# MainBoard_MCU_Power.net
KiCad netlist of a schematic drawn in Altium Designer
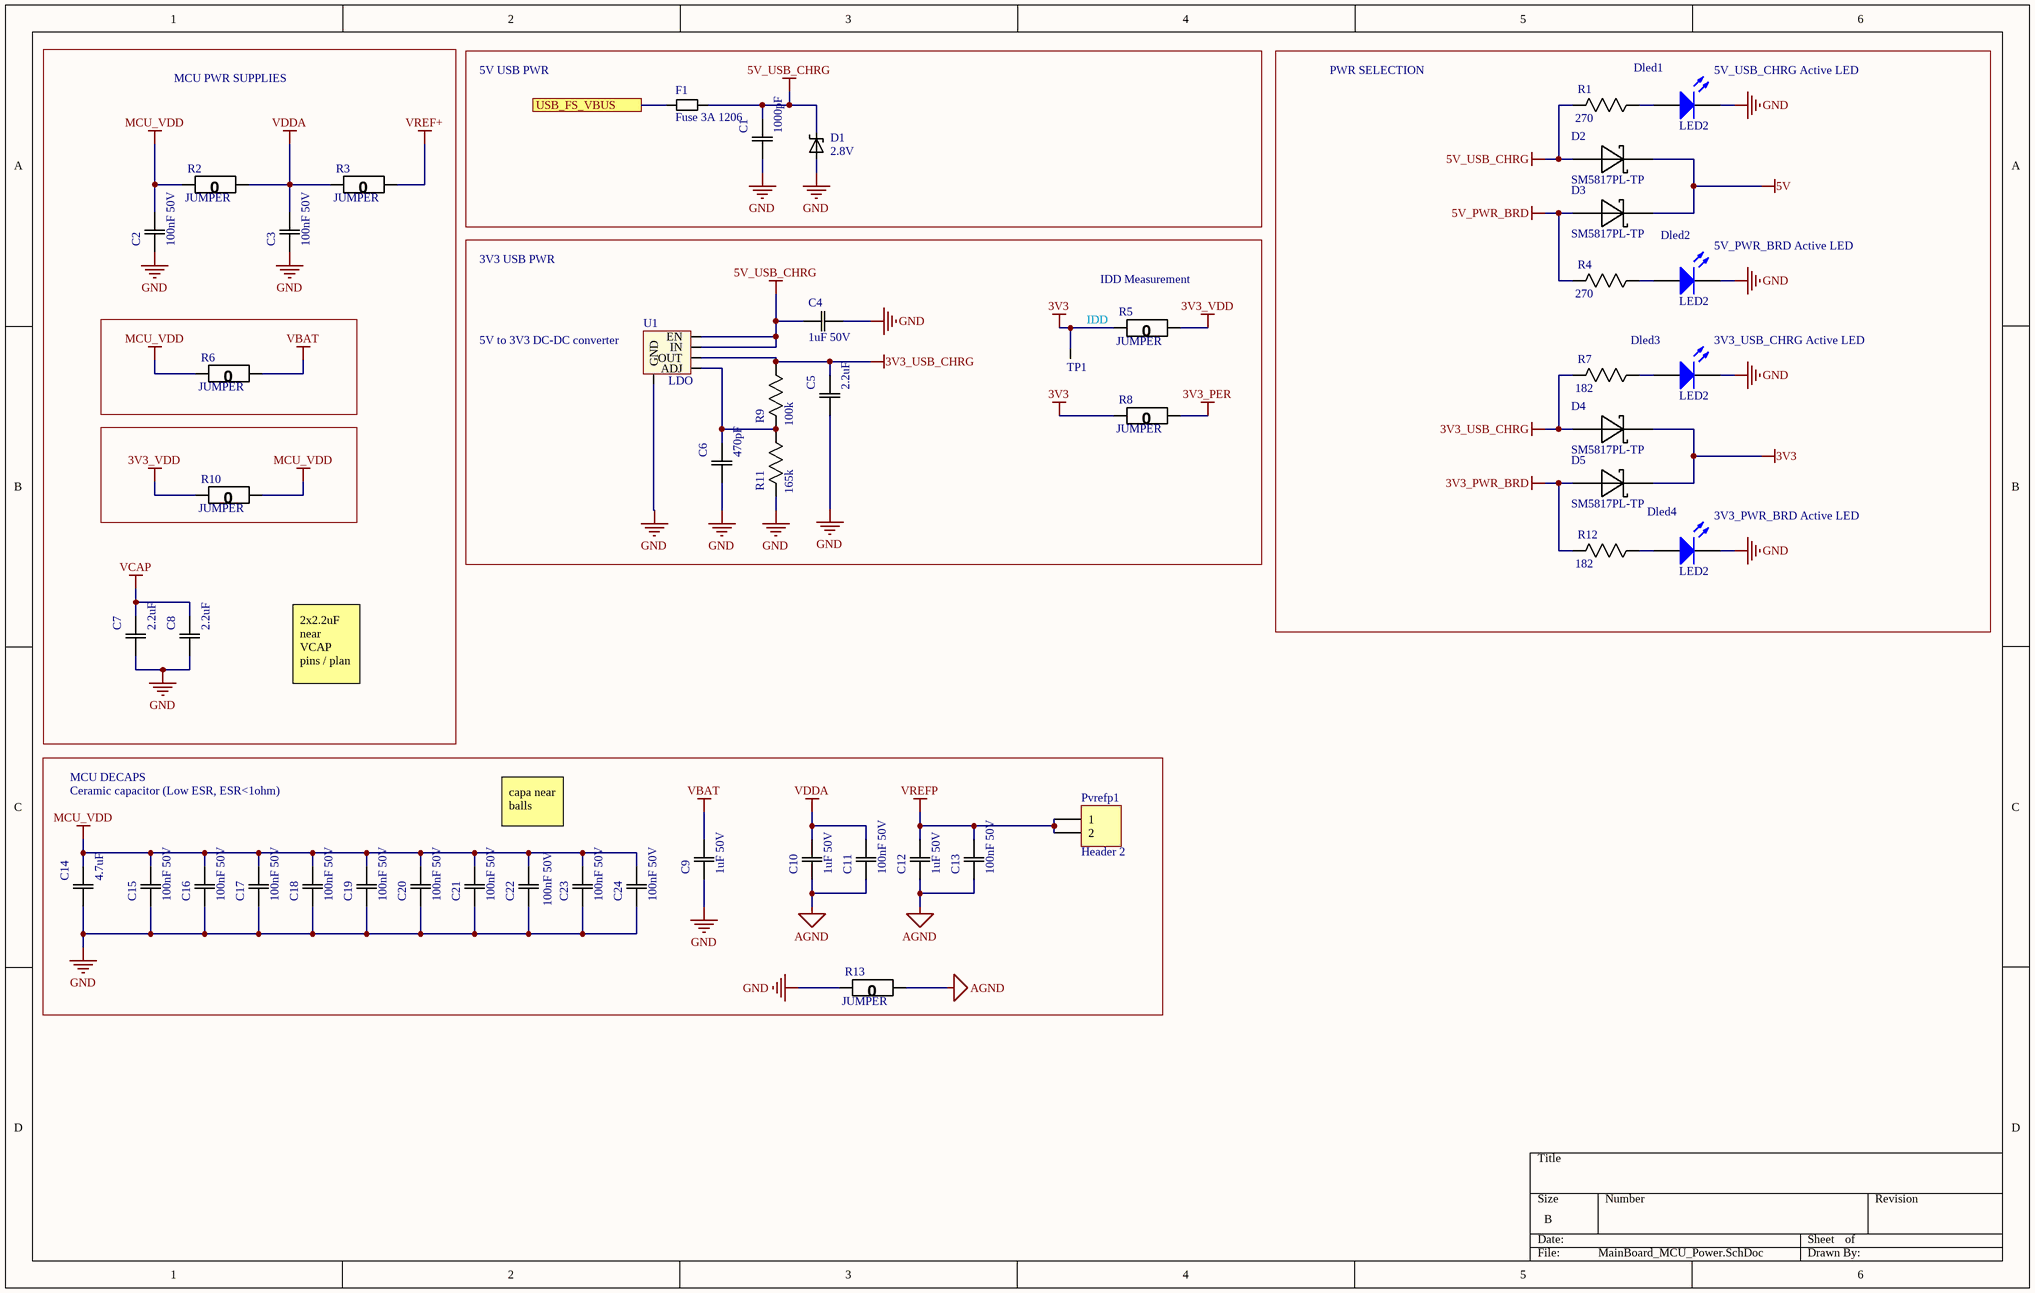
[diagram p0: MainBoard_MCU_Power.SchDoc]

(export (version "E")
  (design (tool "Eeschema 10.0.6"))
  (components
    (comp (ref "C1")
      (value "1000pF")
      (footprint "0805")
      (description "CAP CER 1000PF 50V X7R 0603/0805")
      (fields (field (name "TOLERANCE") "10%"))
      (libsource (lib "AltiumLibraries") (part "CAP 1000pF 50V"))
    )
    (comp (ref "C2")
      (value "100nF 50V")
      (footprint "0805")
      (description "CAP CER 0.1UF 50V X7R 0805")
      (fields (field (name "TOLERANCE") "10%"))
      (libsource (lib "AltiumLibraries") (part "CAP 100nF 50V"))
    )
    (comp (ref "C3")
      (value "100nF 50V")
      (footprint "0805")
      (description "CAP CER 0.1UF 50V X7R 0805")
      (fields (field (name "TOLERANCE") "10%"))
      (libsource (lib "AltiumLibraries") (part "CAP 100nF 50V"))
    )
    (comp (ref "C4")
      (value "1uF 50V")
      (footprint "0805")
      (description "CAP CER 1UF 50V X7R 0805")
      (fields (field (name "TOLERANCE") "10%"))
      (libsource (lib "AltiumLibraries") (part "CAP 1uF 50V"))
    )
    (comp (ref "C5")
      (value "2.2uF")
      (footprint "0805")
      (description "CAP CER 2.2UF 35V X7R 0603/0805")
      (fields (field (name "TOLERANCE") "10%"))
      (libsource (lib "") (part "CAP 2.2uF 35V_1"))
    )
    (comp (ref "C6")
      (value "470pF")
      (footprint "0805")
      (description "CAP CER 470PF 50V X7R 0603/0805")
      (fields (field (name "TOLERANCE") "10%"))
      (libsource (lib "AltiumLibraries") (part "CAP 470pF 50V"))
    )
    (comp (ref "C7")
      (value "2.2uF")
      (footprint "0805")
      (description "CAP CER 2.2UF 35V X7R 0603/0805")
      (fields (field (name "TOLERANCE") "10%"))
      (libsource (lib "AltiumLibraries") (part "CAP 2.2uF 35V"))
    )
    (comp (ref "C8")
      (value "2.2uF")
      (footprint "0805")
      (description "CAP CER 2.2UF 35V X7R 0603/0805")
      (fields (field (name "TOLERANCE") "10%"))
      (libsource (lib "AltiumLibraries") (part "CAP 2.2uF 35V"))
    )
    (comp (ref "C9")
      (value "1uF 50V")
      (footprint "0805")
      (description "CAP CER 1UF 50V X7R 0805")
      (fields (field (name "TOLERANCE") "10%"))
      (libsource (lib "AltiumLibraries") (part "CAP 1uF 50V"))
    )
    (comp (ref "C10")
      (value "1uF 50V")
      (footprint "0805")
      (description "CAP CER 1UF 50V X7R 0805")
      (fields (field (name "TOLERANCE") "10%"))
      (libsource (lib "AltiumLibraries") (part "CAP 1uF 50V"))
    )
    (comp (ref "C11")
      (value "100nF 50V")
      (footprint "0805")
      (description "CAP CER 0.1UF 50V X7R 0805")
      (fields (field (name "TOLERANCE") "10%"))
      (libsource (lib "AltiumLibraries") (part "CAP 100nF 50V"))
    )
    (comp (ref "C12")
      (value "1uF 50V")
      (footprint "0805")
      (description "CAP CER 1UF 50V X7R 0805")
      (fields (field (name "TOLERANCE") "10%"))
      (libsource (lib "AltiumLibraries") (part "CAP 1uF 50V"))
    )
    (comp (ref "C13")
      (value "100nF 50V")
      (footprint "0805")
      (description "CAP CER 0.1UF 50V X7R 0805")
      (fields (field (name "TOLERANCE") "10%"))
      (libsource (lib "AltiumLibraries") (part "CAP 100nF 50V"))
    )
    (comp (ref "C14")
      (value "4.7uF")
      (footprint "0805")
      (description "CAP CER 4.7UF 35V X7R 0603/0805")
      (fields (field (name "TOLERANCE") "10%"))
      (libsource (lib "AltiumLibraries") (part "CAP 4.7uF 35V"))
    )
    (comp (ref "C15")
      (value "100nF 50V")
      (footprint "0805")
      (description "CAP CER 0.1UF 50V X7R 0805")
      (fields (field (name "TOLERANCE") "10%"))
      (libsource (lib "AltiumLibraries") (part "CAP 100nF 50V"))
    )
    (comp (ref "C16")
      (value "100nF 50V")
      (footprint "0805")
      (description "CAP CER 0.1UF 50V X7R 0805")
      (fields (field (name "TOLERANCE") "10%"))
      (libsource (lib "AltiumLibraries") (part "CAP 100nF 50V"))
    )
    (comp (ref "C17")
      (value "100nF 50V")
      (footprint "0805")
      (description "CAP CER 0.1UF 50V X7R 0805")
      (fields (field (name "TOLERANCE") "10%"))
      (libsource (lib "AltiumLibraries") (part "CAP 100nF 50V"))
    )
    (comp (ref "C18")
      (value "100nF 50V")
      (footprint "0805")
      (description "CAP CER 0.1UF 50V X7R 0805")
      (fields (field (name "TOLERANCE") "10%"))
      (libsource (lib "AltiumLibraries") (part "CAP 100nF 50V"))
    )
    (comp (ref "C19")
      (value "100nF 50V")
      (footprint "0805")
      (description "CAP CER 0.1UF 50V X7R 0805")
      (fields (field (name "TOLERANCE") "10%"))
      (libsource (lib "AltiumLibraries") (part "CAP 100nF 50V"))
    )
    (comp (ref "C20")
      (value "100nF 50V")
      (footprint "0805")
      (description "CAP CER 0.1UF 50V X7R 0805")
      (fields (field (name "TOLERANCE") "10%"))
      (libsource (lib "AltiumLibraries") (part "CAP 100nF 50V"))
    )
    (comp (ref "C21")
      (value "100nF 50V")
      (footprint "0805")
      (description "CAP CER 0.1UF 50V X7R 0805")
      (fields (field (name "TOLERANCE") "10%"))
      (libsource (lib "AltiumLibraries") (part "CAP 100nF 50V"))
    )
    (comp (ref "C22")
      (value "100nF 50V")
      (footprint "0805")
      (description "CAP CER 0.1UF 50V X7R 0805")
      (fields (field (name "TOLERANCE") "10%"))
      (libsource (lib "AltiumLibraries") (part "CAP 100nF 50V"))
    )
    (comp (ref "C23")
      (value "100nF 50V")
      (footprint "0805")
      (description "CAP CER 0.1UF 50V X7R 0805")
      (fields (field (name "TOLERANCE") "10%"))
      (libsource (lib "AltiumLibraries") (part "CAP 100nF 50V"))
    )
    (comp (ref "C24")
      (value "100nF 50V")
      (footprint "0805")
      (description "CAP CER 0.1UF 50V X7R 0805")
      (fields (field (name "TOLERANCE") "10%"))
      (libsource (lib "AltiumLibraries") (part "CAP 100nF 50V"))
    )
    (comp (ref "D1")
      (value "2.8V")
      (footprint "SOD-123")
      (description "Zener Diode 2.8V 500mW ±5% Surface Mount SOD-123")
      (libsource (lib "AltiumLibraries") (part "DIODE ZENER 2.8V 500mW"))
    )
    (comp (ref "D2")
      (value "SM5817PL-TP")
      (footprint "SOD-123")
      (description "Diode Schottky 20V 1A Surface Mount SOD-123FL")
      (fields (field (name "MF") "Micro Commercial Co"))
      (libsource (lib "AltiumLibraries") (part "DIODE SCHOTTKY 20V 1A"))
    )
    (comp (ref "D3")
      (value "SM5817PL-TP")
      (footprint "SOD-123")
      (description "Diode Schottky 20V 1A Surface Mount SOD-123FL")
      (fields (field (name "MF") "Micro Commercial Co"))
      (libsource (lib "AltiumLibraries") (part "DIODE SCHOTTKY 20V 1A"))
    )
    (comp (ref "D4")
      (value "SM5817PL-TP")
      (footprint "SOD-123")
      (description "Diode Schottky 20V 1A Surface Mount SOD-123FL")
      (fields (field (name "MF") "Micro Commercial Co"))
      (libsource (lib "AltiumLibraries") (part "DIODE SCHOTTKY 20V 1A"))
    )
    (comp (ref "D5")
      (value "SM5817PL-TP")
      (footprint "SOD-123")
      (description "Diode Schottky 20V 1A Surface Mount SOD-123FL")
      (fields (field (name "MF") "Micro Commercial Co"))
      (libsource (lib "AltiumLibraries") (part "DIODE SCHOTTKY 20V 1A"))
    )
    (comp (ref "Dled1")
      (value "LED2")
      (footprint "3.2X1.6X1.1")
      (description "Typical RED, GREEN, YELLOW, AMBER GaAs LED")
      (libsource (lib "AltiumLibraries") (part "LED GREEN SMD"))
    )
    (comp (ref "Dled2")
      (value "LED2")
      (footprint "3.2X1.6X1.1")
      (description "Typical RED, GREEN, YELLOW, AMBER GaAs LED")
      (libsource (lib "AltiumLibraries") (part "LED GREEN SMD"))
    )
    (comp (ref "Dled3")
      (value "LED2")
      (footprint "3.2X1.6X1.1")
      (description "Typical RED, GREEN, YELLOW, AMBER GaAs LED")
      (libsource (lib "AltiumLibraries") (part "LED GREEN SMD"))
    )
    (comp (ref "Dled4")
      (value "LED2")
      (footprint "3.2X1.6X1.1")
      (description "Typical RED, GREEN, YELLOW, AMBER GaAs LED")
      (libsource (lib "AltiumLibraries") (part "LED GREEN SMD"))
    )
    (comp (ref "F1")
      (value "Fuse 3A 1206")
      (footprint "1206")
      (description "FUSE 3A 63V AC/DC SLOW 1206")
      (libsource (lib "AltiumLibraries") (part "FUSE 3A 63V SLOW"))
    )
    (comp (ref "Pvrefp1")
      (value "Header 2")
      (footprint "HDR1X2")
      (description "Header, 2-Pin")
      (fields (field (name "PUBLISHER") "Altium Limited"))
      (libsource (lib "Miscellaneous Connectors") (part "Header 2"))
    )
    (comp (ref "R1")
      (value "270")
      (footprint "0805")
      (description "RES SMD 270 OHM 5% 1/8W 0805")
      (fields (field (name "TOLERANCE") "5%"))
      (libsource (lib "AltiumLibraries") (part "RES 270.0 1/8W"))
    )
    (comp (ref "R2")
      (value "JUMPER")
      (footprint "0805")
      (description "RES SMD 0 OHM JUMPER GENERIC 0805")
      (libsource (lib "AltiumLibraries") (part "RES 0 JUMPER"))
    )
    (comp (ref "R3")
      (value "JUMPER")
      (footprint "0805")
      (description "RES SMD 0 OHM JUMPER GENERIC 0805")
      (libsource (lib "AltiumLibraries") (part "RES 0 JUMPER"))
    )
    (comp (ref "R4")
      (value "270")
      (footprint "0805")
      (description "RES SMD 270 OHM 5% 1/8W 0805")
      (fields (field (name "TOLERANCE") "5%"))
      (libsource (lib "AltiumLibraries") (part "RES 270.0 1/8W"))
    )
    (comp (ref "R5")
      (value "JUMPER")
      (footprint "0805")
      (description "RES SMD 0 OHM JUMPER GENERIC 0805")
      (libsource (lib "AltiumLibraries") (part "RES 0 JUMPER"))
    )
    (comp (ref "R6")
      (value "JUMPER")
      (footprint "0805")
      (description "RES SMD 0 OHM JUMPER GENERIC 0805")
      (libsource (lib "AltiumLibraries") (part "RES 0 JUMPER"))
    )
    (comp (ref "R7")
      (value "182")
      (footprint "0805")
      (description "RES SMD 182 OHM 1% 1/8W 0805")
      (fields (field (name "TOLERANCE") "1%"))
      (libsource (lib "AltiumLibraries") (part "RES 182.0 1/8W"))
    )
    (comp (ref "R8")
      (value "JUMPER")
      (footprint "0805")
      (description "RES SMD 0 OHM JUMPER GENERIC 0805")
      (libsource (lib "AltiumLibraries") (part "RES 0 JUMPER"))
    )
    (comp (ref "R9")
      (value "100k")
      (footprint "0805")
      (description "RES SMD 100K OHM 5% 1/8W 0805")
      (fields (field (name "TOLERANCE") "5%"))
      (libsource (lib "AltiumLibraries") (part "RES 100k 1/8W - 5%"))
    )
    (comp (ref "R10")
      (value "JUMPER")
      (footprint "0805")
      (description "RES SMD 0 OHM JUMPER GENERIC 0805")
      (libsource (lib "AltiumLibraries") (part "RES 0 JUMPER"))
    )
    (comp (ref "R11")
      (value "165k")
      (footprint "0805")
      (description "RES SMD 165K OHM 1% 1/4W 0805")
      (fields (field (name "TOLERANCE") "1%"))
      (libsource (lib "AltiumLibraries") (part "RES 165k 1/4W"))
    )
    (comp (ref "R12")
      (value "182")
      (footprint "0805")
      (description "RES SMD 182 OHM 1% 1/8W 0805")
      (fields (field (name "TOLERANCE") "1%"))
      (libsource (lib "AltiumLibraries") (part "RES 182.0 1/8W"))
    )
    (comp (ref "R13")
      (value "JUMPER")
      (footprint "0805")
      (description "RES SMD 0 OHM JUMPER GENERIC 0805")
      (libsource (lib "AltiumLibraries") (part "RES 0 JUMPER"))
    )
    (comp (ref "TP1")
      (value "Test Point (Via)")
      (footprint "TP")
      (libsource (lib "AltiumLibraries") (part "Test Point (Via)"))
    )
    (comp (ref "U1")
      (value "LDO")
      (footprint "REG LIN POS ADJ 500MA 8SOIC")
      (description "Linear Voltage Regulator IC  1 Output  500mA 8-SOIC")
      (fields (field (name "MF") "Texas Instruments") (field (name "MP") "TL5209DR"))
      (libsource (lib "AltiumLibraries") (part "REG LIN POS ADJ"))
    )
  )
  (nets
    (net (code "1") (name "/USB_FS_VBUS") (class "Default")
      (node (ref "F1") (pin "1") (pinfunction "1_1") (pintype "passive"))
    )
    (net (code "2") (name "3V3") (class "Default")
      (node (ref "D4") (pin "C") (pinfunction "K_C") (pintype "passive"))
      (node (ref "D5") (pin "C") (pinfunction "K_C") (pintype "passive"))
      (node (ref "R5") (pin "2") (pinfunction "R2_2") (pintype "passive"))
      (node (ref "R8") (pin "2") (pinfunction "R2_2") (pintype "passive"))
      (node (ref "TP1") (pin "1") (pinfunction "1_1") (pintype "passive"))
    )
    (net (code "3") (name "3V3_PER") (class "Default")
      (node (ref "R8") (pin "1") (pinfunction "R1_1") (pintype "passive"))
    )
    (net (code "4") (name "3V3_PWR_BRD") (class "Default")
      (node (ref "D5") (pin "A") (pinfunction "A_A") (pintype "passive"))
      (node (ref "R12") (pin "2") (pinfunction "R2_2") (pintype "passive"))
    )
    (net (code "5") (name "3V3_USB_CHRG") (class "Default")
      (node (ref "C5") (pin "2") (pinfunction "C2_2") (pintype "passive"))
      (node (ref "D4") (pin "A") (pinfunction "A_A") (pintype "passive"))
      (node (ref "R7") (pin "2") (pinfunction "R2_2") (pintype "passive"))
      (node (ref "R9") (pin "1") (pinfunction "R1_1") (pintype "passive"))
      (node (ref "U1") (pin "OUT") (pinfunction "OUT_OUT") (pintype "passive"))
    )
    (net (code "6") (name "3V3_VDD") (class "Default")
      (node (ref "R10") (pin "2") (pinfunction "R2_2") (pintype "passive"))
      (node (ref "R5") (pin "1") (pinfunction "R1_1") (pintype "passive"))
    )
    (net (code "7") (name "5V") (class "Default")
      (node (ref "D2") (pin "C") (pinfunction "K_C") (pintype "passive"))
      (node (ref "D3") (pin "C") (pinfunction "K_C") (pintype "passive"))
    )
    (net (code "8") (name "5V_PWR_BRD") (class "Default")
      (node (ref "D3") (pin "A") (pinfunction "A_A") (pintype "passive"))
      (node (ref "R4") (pin "2") (pinfunction "R2_2") (pintype "passive"))
    )
    (net (code "9") (name "5V_USB_CHRG") (class "Default")
      (node (ref "C1") (pin "2") (pinfunction "C2_2") (pintype "passive"))
      (node (ref "C4") (pin "1") (pinfunction "C1_1") (pintype "passive"))
      (node (ref "D1") (pin "C") (pinfunction "C_C") (pintype "passive"))
      (node (ref "D2") (pin "A") (pinfunction "A_A") (pintype "passive"))
      (node (ref "F1") (pin "2") (pinfunction "2_2") (pintype "passive"))
      (node (ref "R1") (pin "2") (pinfunction "R2_2") (pintype "passive"))
      (node (ref "U1") (pin "EN") (pinfunction "EN_EN") (pintype "passive"))
      (node (ref "U1") (pin "IN") (pinfunction "IN_IN") (pintype "passive"))
    )
    (net (code "10") (name "AGND") (class "Default")
      (node (ref "C10") (pin "1") (pinfunction "C1_1") (pintype "passive"))
      (node (ref "C11") (pin "1") (pinfunction "C1_1") (pintype "passive"))
      (node (ref "C12") (pin "1") (pinfunction "C1_1") (pintype "passive"))
      (node (ref "C13") (pin "1") (pinfunction "C1_1") (pintype "passive"))
      (node (ref "R13") (pin "1") (pinfunction "R1_1") (pintype "passive"))
    )
    (net (code "11") (name "GND") (class "Default")
      (node (ref "C1") (pin "1") (pinfunction "C1_1") (pintype "passive"))
      (node (ref "C14") (pin "1") (pinfunction "C1_1") (pintype "passive"))
      (node (ref "C15") (pin "1") (pinfunction "C1_1") (pintype "passive"))
      (node (ref "C16") (pin "1") (pinfunction "C1_1") (pintype "passive"))
      (node (ref "C17") (pin "1") (pinfunction "C1_1") (pintype "passive"))
      (node (ref "C18") (pin "1") (pinfunction "C1_1") (pintype "passive"))
      (node (ref "C19") (pin "1") (pinfunction "C1_1") (pintype "passive"))
      (node (ref "C2") (pin "1") (pinfunction "C1_1") (pintype "passive"))
      (node (ref "C20") (pin "1") (pinfunction "C1_1") (pintype "passive"))
      (node (ref "C21") (pin "1") (pinfunction "C1_1") (pintype "passive"))
      (node (ref "C22") (pin "1") (pinfunction "C1_1") (pintype "passive"))
      (node (ref "C23") (pin "1") (pinfunction "C1_1") (pintype "passive"))
      (node (ref "C24") (pin "1") (pinfunction "C1_1") (pintype "passive"))
      (node (ref "C3") (pin "1") (pinfunction "C1_1") (pintype "passive"))
      (node (ref "C4") (pin "2") (pinfunction "C2_2") (pintype "passive"))
      (node (ref "C5") (pin "1") (pinfunction "C1_1") (pintype "passive"))
      (node (ref "C6") (pin "1") (pinfunction "C1_1") (pintype "passive"))
      (node (ref "C7") (pin "1") (pinfunction "C1_1") (pintype "passive"))
      (node (ref "C8") (pin "1") (pinfunction "C1_1") (pintype "passive"))
      (node (ref "C9") (pin "1") (pinfunction "C1_1") (pintype "passive"))
      (node (ref "D1") (pin "A") (pinfunction "A_A") (pintype "passive"))
      (node (ref "Dled1") (pin "2") (pinfunction "K_2") (pintype "passive"))
      (node (ref "Dled2") (pin "2") (pinfunction "K_2") (pintype "passive"))
      (node (ref "Dled3") (pin "2") (pinfunction "K_2") (pintype "passive"))
      (node (ref "Dled4") (pin "2") (pinfunction "K_2") (pintype "passive"))
      (node (ref "R11") (pin "2") (pinfunction "R2_2") (pintype "passive"))
      (node (ref "R13") (pin "2") (pinfunction "R2_2") (pintype "passive"))
      (node (ref "U1") (pin "GND") (pinfunction "GND_GND") (pintype "passive"))
    )
    (net (code "12") (name "MCU_VDD") (class "Default")
      (node (ref "C14") (pin "2") (pinfunction "C2_2") (pintype "passive"))
      (node (ref "C15") (pin "2") (pinfunction "C2_2") (pintype "passive"))
      (node (ref "C16") (pin "2") (pinfunction "C2_2") (pintype "passive"))
      (node (ref "C17") (pin "2") (pinfunction "C2_2") (pintype "passive"))
      (node (ref "C18") (pin "2") (pinfunction "C2_2") (pintype "passive"))
      (node (ref "C19") (pin "2") (pinfunction "C2_2") (pintype "passive"))
      (node (ref "C2") (pin "2") (pinfunction "C2_2") (pintype "passive"))
      (node (ref "C20") (pin "2") (pinfunction "C2_2") (pintype "passive"))
      (node (ref "C21") (pin "2") (pinfunction "C2_2") (pintype "passive"))
      (node (ref "C22") (pin "2") (pinfunction "C2_2") (pintype "passive"))
      (node (ref "C23") (pin "2") (pinfunction "C2_2") (pintype "passive"))
      (node (ref "C24") (pin "2") (pinfunction "C2_2") (pintype "passive"))
      (node (ref "R10") (pin "1") (pinfunction "R1_1") (pintype "passive"))
      (node (ref "R2") (pin "2") (pinfunction "R2_2") (pintype "passive"))
      (node (ref "R6") (pin "2") (pinfunction "R2_2") (pintype "passive"))
    )
    (net (code "13") (name "Net-(C6-C2)") (class "Default")
      (node (ref "C6") (pin "2") (pinfunction "C2_2") (pintype "passive"))
      (node (ref "R11") (pin "1") (pinfunction "R1_1") (pintype "passive"))
      (node (ref "R9") (pin "2") (pinfunction "R2_2") (pintype "passive"))
      (node (ref "U1") (pin "ADJ") (pinfunction "ADJ_ADJ") (pintype "passive"))
    )
    (net (code "14") (name "Net-(Dled1-A)") (class "Default")
      (node (ref "Dled1") (pin "1") (pinfunction "A_1") (pintype "passive"))
      (node (ref "R1") (pin "1") (pinfunction "R1_1") (pintype "passive"))
    )
    (net (code "15") (name "Net-(Dled2-A)") (class "Default")
      (node (ref "Dled2") (pin "1") (pinfunction "A_1") (pintype "passive"))
      (node (ref "R4") (pin "1") (pinfunction "R1_1") (pintype "passive"))
    )
    (net (code "16") (name "Net-(Dled3-A)") (class "Default")
      (node (ref "Dled3") (pin "1") (pinfunction "A_1") (pintype "passive"))
      (node (ref "R7") (pin "1") (pinfunction "R1_1") (pintype "passive"))
    )
    (net (code "17") (name "Net-(Dled4-A)") (class "Default")
      (node (ref "Dled4") (pin "1") (pinfunction "A_1") (pintype "passive"))
      (node (ref "R12") (pin "1") (pinfunction "R1_1") (pintype "passive"))
    )
    (net (code "18") (name "VBAT") (class "Default")
      (node (ref "C9") (pin "2") (pinfunction "C2_2") (pintype "passive"))
      (node (ref "R6") (pin "1") (pinfunction "R1_1") (pintype "passive"))
    )
    (net (code "19") (name "VCAP") (class "Default")
      (node (ref "C7") (pin "2") (pinfunction "C2_2") (pintype "passive"))
      (node (ref "C8") (pin "2") (pinfunction "C2_2") (pintype "passive"))
    )
    (net (code "20") (name "VDDA") (class "Default")
      (node (ref "C10") (pin "2") (pinfunction "C2_2") (pintype "passive"))
      (node (ref "C11") (pin "2") (pinfunction "C2_2") (pintype "passive"))
      (node (ref "C3") (pin "2") (pinfunction "C2_2") (pintype "passive"))
      (node (ref "R2") (pin "1") (pinfunction "R1_1") (pintype "passive"))
      (node (ref "R3") (pin "2") (pinfunction "R2_2") (pintype "passive"))
    )
    (net (code "21") (name "VREF+") (class "Default")
      (node (ref "R3") (pin "1") (pinfunction "R1_1") (pintype "passive"))
    )
    (net (code "22") (name "VREFP") (class "Default")
      (node (ref "C12") (pin "2") (pinfunction "C2_2") (pintype "passive"))
      (node (ref "C13") (pin "2") (pinfunction "C2_2") (pintype "passive"))
      (node (ref "Pvrefp1") (pin "1") (pinfunction "1_1") (pintype "passive"))
      (node (ref "Pvrefp1") (pin "2") (pinfunction "2_2") (pintype "passive"))
    )
  )
)
